# esp-wroom-02_conv_board.net
KiCad netlist of a schematic drawn in EAGLE
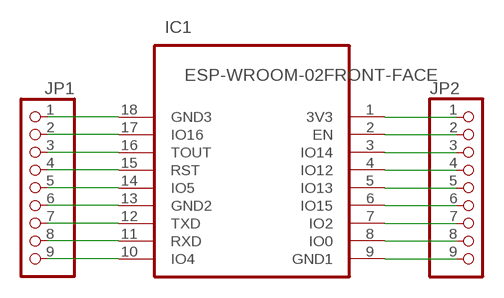
[diagram p0: schematic, sheet 1]

(export (version "E")
  (design (tool "Eeschema 10.0.6"))
  (components
    (comp (ref "IC1")
      (value "ESP-WROOM-02FRONT-FACE")
      (footprint "eagle-import:FRONT-FACE")
      (libsource (lib "eagle-import") (part "ESP-WROOM-02FRONT-FACE"))
    )
    (comp (ref "JP1")
      (value "PINHD-1X9")
      (footprint "eagle-import:1X09")
      (libsource (lib "eagle-import") (part "PINHD-1X9"))
    )
    (comp (ref "JP2")
      (value "PINHD-1X9")
      (footprint "eagle-import:1X09")
      (libsource (lib "eagle-import") (part "PINHD-1X9"))
    )
  )
  (nets
    (net (code "1") (name "Net-(IC1-3V3)") (class "Default")
      (node (ref "IC1") (pin "1") (pinfunction "3V3_1") (pintype "power_in"))
      (node (ref "JP2") (pin "1") (pinfunction "1_1") (pintype "passive"))
    )
    (net (code "2") (name "Net-(IC1-EN)") (class "Default")
      (node (ref "IC1") (pin "2") (pinfunction "EN_2") (pintype "bidirectional"))
      (node (ref "JP2") (pin "2") (pinfunction "2_2") (pintype "passive"))
    )
    (net (code "3") (name "Net-(IC1-GND1)") (class "Default")
      (node (ref "IC1") (pin "9") (pinfunction "GND1_9") (pintype "power_in"))
      (node (ref "JP2") (pin "9") (pinfunction "9_9") (pintype "passive"))
    )
    (net (code "4") (name "Net-(IC1-GND2)") (class "Default")
      (node (ref "IC1") (pin "13") (pinfunction "GND2_13") (pintype "power_in"))
      (node (ref "JP1") (pin "6") (pinfunction "6_6") (pintype "passive"))
    )
    (net (code "5") (name "Net-(IC1-GND3)") (class "Default")
      (node (ref "IC1") (pin "18") (pinfunction "GND3_18") (pintype "power_in"))
      (node (ref "JP1") (pin "1") (pinfunction "1_1") (pintype "passive"))
    )
    (net (code "6") (name "Net-(IC1-IO0)") (class "Default")
      (node (ref "IC1") (pin "8") (pinfunction "IO0_8") (pintype "bidirectional"))
      (node (ref "JP2") (pin "8") (pinfunction "8_8") (pintype "passive"))
    )
    (net (code "7") (name "Net-(IC1-IO2)") (class "Default")
      (node (ref "IC1") (pin "7") (pinfunction "IO2_7") (pintype "bidirectional"))
      (node (ref "JP2") (pin "7") (pinfunction "7_7") (pintype "passive"))
    )
    (net (code "8") (name "Net-(IC1-IO4)") (class "Default")
      (node (ref "IC1") (pin "10") (pinfunction "IO4_10") (pintype "bidirectional"))
      (node (ref "JP1") (pin "9") (pinfunction "9_9") (pintype "passive"))
    )
    (net (code "9") (name "Net-(IC1-IO5)") (class "Default")
      (node (ref "IC1") (pin "14") (pinfunction "IO5_14") (pintype "open_collector"))
      (node (ref "JP1") (pin "5") (pinfunction "5_5") (pintype "passive"))
    )
    (net (code "10") (name "Net-(IC1-IO12)") (class "Default")
      (node (ref "IC1") (pin "4") (pinfunction "IO12_4") (pintype "bidirectional"))
      (node (ref "JP2") (pin "4") (pinfunction "4_4") (pintype "passive"))
    )
    (net (code "11") (name "Net-(IC1-IO13)") (class "Default")
      (node (ref "IC1") (pin "5") (pinfunction "IO13_5") (pintype "bidirectional"))
      (node (ref "JP2") (pin "5") (pinfunction "5_5") (pintype "passive"))
    )
    (net (code "12") (name "Net-(IC1-IO14)") (class "Default")
      (node (ref "IC1") (pin "3") (pinfunction "IO14_3") (pintype "bidirectional"))
      (node (ref "JP2") (pin "3") (pinfunction "3_3") (pintype "passive"))
    )
    (net (code "13") (name "Net-(IC1-IO15)") (class "Default")
      (node (ref "IC1") (pin "6") (pinfunction "IO15_6") (pintype "bidirectional"))
      (node (ref "JP2") (pin "6") (pinfunction "6_6") (pintype "passive"))
    )
    (net (code "14") (name "Net-(IC1-IO16)") (class "Default")
      (node (ref "IC1") (pin "17") (pinfunction "IO16_17") (pintype "bidirectional"))
      (node (ref "JP1") (pin "2") (pinfunction "2_2") (pintype "passive"))
    )
    (net (code "15") (name "Net-(IC1-RST)") (class "Default")
      (node (ref "IC1") (pin "15") (pinfunction "RST_15") (pintype "bidirectional"))
      (node (ref "JP1") (pin "4") (pinfunction "4_4") (pintype "passive"))
    )
    (net (code "16") (name "Net-(IC1-RXD)") (class "Default")
      (node (ref "IC1") (pin "11") (pinfunction "RXD_11") (pintype "bidirectional"))
      (node (ref "JP1") (pin "8") (pinfunction "8_8") (pintype "passive"))
    )
    (net (code "17") (name "Net-(IC1-TOUT)") (class "Default")
      (node (ref "IC1") (pin "16") (pinfunction "TOUT_16") (pintype "bidirectional"))
      (node (ref "JP1") (pin "3") (pinfunction "3_3") (pintype "passive"))
    )
    (net (code "18") (name "Net-(IC1-TXD)") (class "Default")
      (node (ref "IC1") (pin "12") (pinfunction "TXD_12") (pintype "bidirectional"))
      (node (ref "JP1") (pin "7") (pinfunction "7_7") (pintype "passive"))
    )
  )
)
